# Seeed_Studio_Round_Display_for_XIAO_v1_0.net
KiCad netlist of a schematic drawn in EAGLE
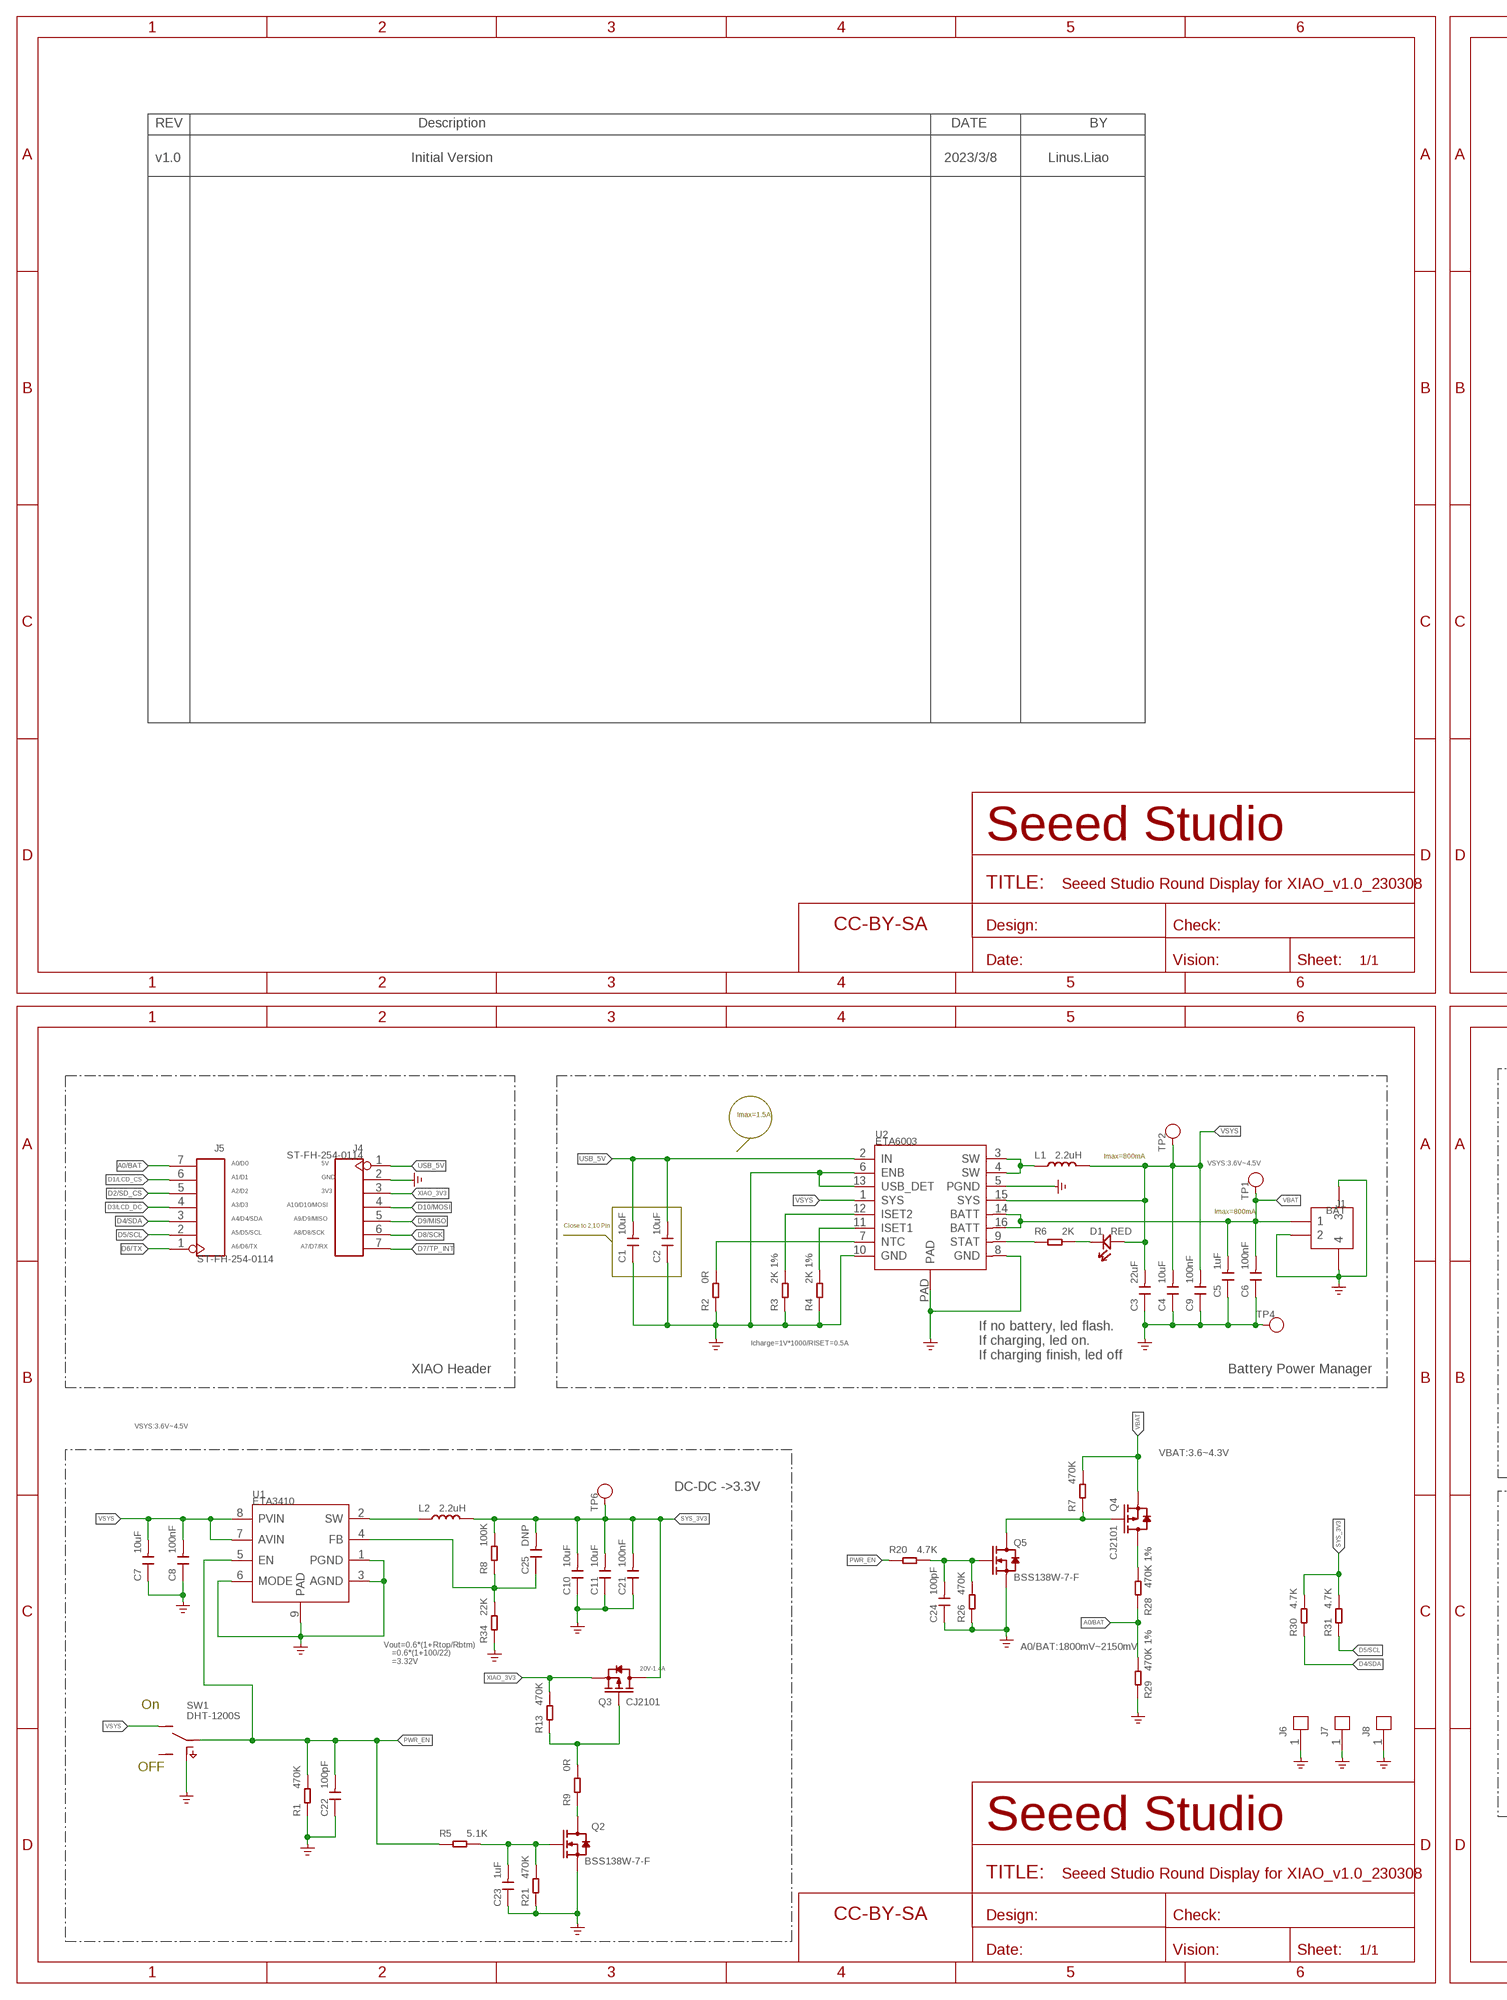
[diagram p0: schematic, sheet 1, part 1 of 2]
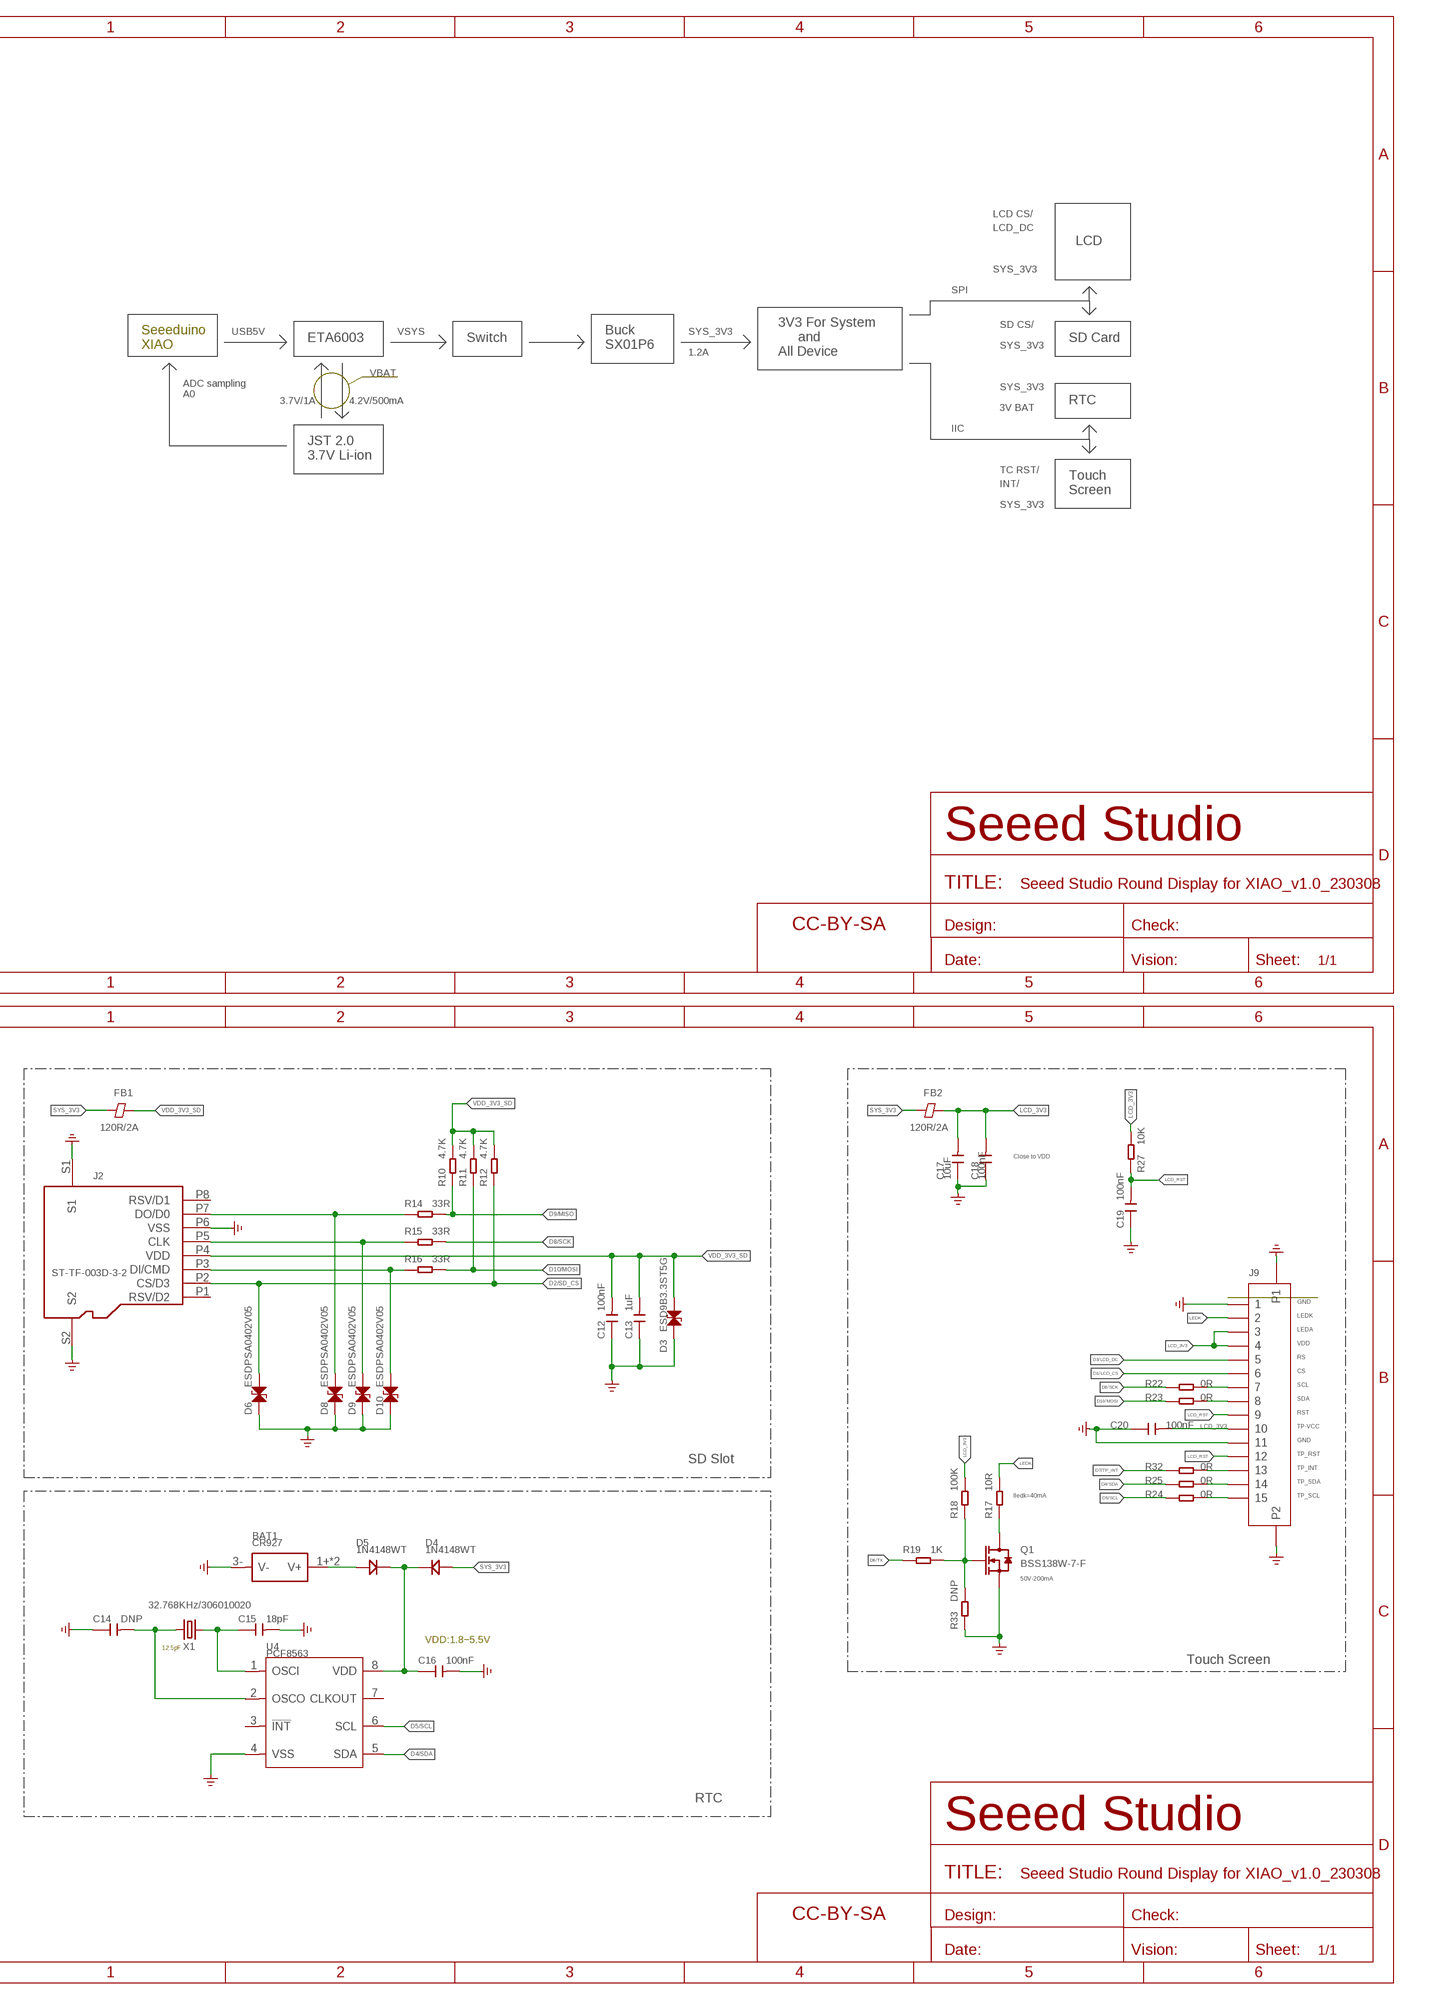
[diagram p1: schematic, sheet 1, part 2 of 2]

(export (version "E")
  (design (tool "Eeschema 10.0.6"))
  (components
    (comp (ref "BAT1")
      (value "CR927")
      (footprint "eagle-import:BAT2P-SMD-15.3X8.6X2.9MM")
      (libsource (lib "eagle-import") (part "BAT-HOLDER-CR927"))
    )
    (comp (ref "C1")
      (value "10uF")
      (footprint "eagle-import:C0603")
      (libsource (lib "eagle-import") (part "CAP-0603"))
    )
    (comp (ref "C2")
      (value "10uF")
      (footprint "eagle-import:C0603")
      (libsource (lib "eagle-import") (part "CAP-0603"))
    )
    (comp (ref "C3")
      (value "22uF")
      (footprint "eagle-import:C0603")
      (libsource (lib "eagle-import") (part "CAP-0603"))
    )
    (comp (ref "C4")
      (value "10uF")
      (footprint "eagle-import:C0603")
      (libsource (lib "eagle-import") (part "CAP-0603"))
    )
    (comp (ref "C5")
      (value "1uF")
      (footprint "eagle-import:C0402")
      (libsource (lib "eagle-import") (part "CAP-0402"))
    )
    (comp (ref "C6")
      (value "100nF")
      (footprint "eagle-import:C0402")
      (libsource (lib "eagle-import") (part "CAP-0402"))
    )
    (comp (ref "C7")
      (value "10uF")
      (footprint "eagle-import:C0603")
      (libsource (lib "eagle-import") (part "CAP-0603"))
    )
    (comp (ref "C8")
      (value "100nF")
      (footprint "eagle-import:C0402")
      (libsource (lib "eagle-import") (part "CAP-0402"))
    )
    (comp (ref "C9")
      (value "100nF")
      (footprint "eagle-import:C0402")
      (libsource (lib "eagle-import") (part "CAP-0402"))
    )
    (comp (ref "C10")
      (value "10uF")
      (footprint "eagle-import:C0603")
      (libsource (lib "eagle-import") (part "CAP-0603"))
    )
    (comp (ref "C11")
      (value "10uF")
      (footprint "eagle-import:C0603")
      (libsource (lib "eagle-import") (part "CAP-0603"))
    )
    (comp (ref "C12")
      (value "100nF")
      (footprint "eagle-import:C0402")
      (libsource (lib "eagle-import") (part "CAP-0402"))
    )
    (comp (ref "C13")
      (value "1uF")
      (footprint "eagle-import:C0402")
      (libsource (lib "eagle-import") (part "CAP-0402"))
    )
    (comp (ref "C14")
      (value "DNP")
      (footprint "eagle-import:C0402")
      (libsource (lib "eagle-import") (part "CAP-0402"))
    )
    (comp (ref "C15")
      (value "18pF")
      (footprint "eagle-import:C0402")
      (libsource (lib "eagle-import") (part "CAP-0402"))
    )
    (comp (ref "C16")
      (value "100nF")
      (footprint "eagle-import:C0402")
      (libsource (lib "eagle-import") (part "CAP-0402"))
    )
    (comp (ref "C17")
      (value "10uF")
      (footprint "eagle-import:C0402")
      (libsource (lib "eagle-import") (part "CAP-0402"))
    )
    (comp (ref "C18")
      (value "100nF")
      (footprint "eagle-import:C0402")
      (libsource (lib "eagle-import") (part "CAP-0402"))
    )
    (comp (ref "C19")
      (value "100nF")
      (footprint "eagle-import:C0402")
      (libsource (lib "eagle-import") (part "CAP-0402"))
    )
    (comp (ref "C20")
      (value "100nF")
      (footprint "eagle-import:C0402")
      (libsource (lib "eagle-import") (part "CAP-0402"))
    )
    (comp (ref "C21")
      (value "100nF")
      (footprint "eagle-import:C0402")
      (libsource (lib "eagle-import") (part "CAP-0402"))
    )
    (comp (ref "C22")
      (value "100pF")
      (footprint "eagle-import:C0402")
      (libsource (lib "eagle-import") (part "CAP-0402"))
    )
    (comp (ref "C23")
      (value "1uF")
      (footprint "eagle-import:C0402")
      (libsource (lib "eagle-import") (part "CAP-0402"))
    )
    (comp (ref "C24")
      (value "100pF")
      (footprint "eagle-import:C0402")
      (libsource (lib "eagle-import") (part "CAP-0402"))
    )
    (comp (ref "C25")
      (value "DNP")
      (footprint "eagle-import:C0402")
      (libsource (lib "eagle-import") (part "CAP-0402"))
    )
    (comp (ref "D1")
      (value "RED")
      (footprint "eagle-import:LED-0402")
      (libsource (lib "eagle-import") (part "LED-0402"))
    )
    (comp (ref "D3")
      (value "ESD9B3.3ST5G")
      (footprint "eagle-import:ESD-0402")
      (libsource (lib "eagle-import") (part "D-ESD-2P-DOUBLE-0402"))
    )
    (comp (ref "D4")
      (value "1N4148WT")
      (footprint "eagle-import:SOD-523")
      (libsource (lib "eagle-import") (part "DIODE'0603'"))
    )
    (comp (ref "D5")
      (value "1N4148WT")
      (footprint "eagle-import:SOD-523")
      (libsource (lib "eagle-import") (part "DIODE'0603'"))
    )
    (comp (ref "D6")
      (value "ESDPSA0402V05")
      (footprint "eagle-import:ESD-0402")
      (libsource (lib "eagle-import") (part "D-ESD-2P-DOUBLE-0402"))
    )
    (comp (ref "D8")
      (value "ESDPSA0402V05")
      (footprint "eagle-import:ESD-0402")
      (libsource (lib "eagle-import") (part "D-ESD-2P-DOUBLE-0402"))
    )
    (comp (ref "D9")
      (value "ESDPSA0402V05")
      (footprint "eagle-import:ESD-0402")
      (libsource (lib "eagle-import") (part "D-ESD-2P-DOUBLE-0402"))
    )
    (comp (ref "D10")
      (value "ESDPSA0402V05")
      (footprint "eagle-import:ESD-0402")
      (libsource (lib "eagle-import") (part "D-ESD-2P-DOUBLE-0402"))
    )
    (comp (ref "FB1")
      (value "120R/2A")
      (footprint "eagle-import:F0402")
      (libsource (lib "eagle-import") (part "FERRITE-BEAD-0402"))
    )
    (comp (ref "FB2")
      (value "120R/2A")
      (footprint "eagle-import:F0402")
      (libsource (lib "eagle-import") (part "FERRITE-BEAD-0402"))
    )
    (comp (ref "FR1")
      (value "SEEEDSTUDIO-OPEN-SCH-FRAME")
      (footprint "eagle-import:SEEEDSTUDIO-PCB-FRAME")
      (libsource (lib "eagle-import") (part "SEEEDSTUDIO-OPEN-SCH-FRAME"))
    )
    (comp (ref "FR2")
      (value "SEEEDSTUDIO-OPEN-SCH-FRAME")
      (footprint "eagle-import:SEEEDSTUDIO-PCB-FRAME")
      (libsource (lib "eagle-import") (part "SEEEDSTUDIO-OPEN-SCH-FRAME"))
    )
    (comp (ref "FR3")
      (value "SEEEDSTUDIO-OPEN-SCH-FRAME")
      (footprint "eagle-import:SEEEDSTUDIO-PCB-FRAME")
      (libsource (lib "eagle-import") (part "SEEEDSTUDIO-OPEN-SCH-FRAME"))
    )
    (comp (ref "FR4")
      (value "SEEEDSTUDIO-OPEN-SCH-FRAME")
      (footprint "eagle-import:SEEEDSTUDIO-PCB-FRAME")
      (libsource (lib "eagle-import") (part "SEEEDSTUDIO-OPEN-SCH-FRAME"))
    )
    (comp (ref "J1")
      (value "BAT")
      (footprint "eagle-import:HW2+2P-SMD-1.25")
      (libsource (lib "eagle-import") (part "JST-2+2P-1.25"))
    )
    (comp (ref "J2")
      (value "ST-TF-003D-3-2")
      (footprint "eagle-import:MICRO-SD8+2P-SMD-1.1-11.41X4.9X3MM")
      (libsource (lib "eagle-import") (part "MICRO-SD-CARD-HOLDER-SHORT-8P"))
    )
    (comp (ref "J4")
      (value "ST-FH-254-0114")
      (footprint "eagle-import:H7-2.54-18.28X2.5X5MM")
      (libsource (lib "eagle-import") (part "HEADER-7P-18.28X2.5"))
    )
    (comp (ref "J5")
      (value "ST-FH-254-0114")
      (footprint "eagle-import:H7-2.54-18.28X2.5X5MM")
      (libsource (lib "eagle-import") (part "HEADER-7P-18.28X2.5"))
    )
    (comp (ref "J6")
      (value "HEADER-1P-3.5/2.2_PASTE")
      (footprint "eagle-import:H1P-3.5_2.2MM-PASTE")
      (libsource (lib "eagle-import") (part "HEADER-1P-3.5/2.2_PASTE"))
    )
    (comp (ref "J7")
      (value "HEADER-1P-3.5/2.2_PASTE")
      (footprint "eagle-import:H1P-3.5_2.2MM-PASTE")
      (libsource (lib "eagle-import") (part "HEADER-1P-3.5/2.2_PASTE"))
    )
    (comp (ref "J8")
      (value "HEADER-1P-3.5/2.2_PASTE")
      (footprint "eagle-import:H1P-3.5_2.2MM-PASTE")
      (libsource (lib "eagle-import") (part "HEADER-1P-3.5/2.2_PASTE"))
    )
    (comp (ref "J9")
      (value "FPC-CONNECTOR-15P")
      (footprint "eagle-import:FPC15P-0.6-6.1X2.83X1MM")
      (libsource (lib "eagle-import") (part "FPC-CONNECTOR-15P"))
    )
    (comp (ref "L1")
      (value "2.2uH")
      (footprint "eagle-import:L0806")
      (libsource (lib "eagle-import") (part "INDUCTOR'0806'"))
    )
    (comp (ref "L2")
      (value "2.2uH")
      (footprint "eagle-import:L0806")
      (libsource (lib "eagle-import") (part "INDUCTOR'0806'"))
    )
    (comp (ref "Q1")
      (value "BSS138W-7-F")
      (footprint "eagle-import:SOT-323")
      (libsource (lib "eagle-import") (part "MOSFET-N-SI1304BDL"))
    )
    (comp (ref "Q2")
      (value "BSS138W-7-F")
      (footprint "eagle-import:SOT-323")
      (libsource (lib "eagle-import") (part "MOSFET-N-SI1304BDL"))
    )
    (comp (ref "Q3")
      (value "CJ2101")
      (footprint "eagle-import:SOT-323")
      (libsource (lib "eagle-import") (part "MOSFET-P-SOT323"))
    )
    (comp (ref "Q4")
      (value "CJ2101")
      (footprint "eagle-import:SOT-323")
      (libsource (lib "eagle-import") (part "MOSFET-P-SOT323"))
    )
    (comp (ref "Q5")
      (value "BSS138W-7-F")
      (footprint "eagle-import:SOT-323")
      (libsource (lib "eagle-import") (part "MOSFET-N-SI1304BDL"))
    )
    (comp (ref "R1")
      (value "470K")
      (footprint "eagle-import:R0402")
      (libsource (lib "eagle-import") (part "RES-0402"))
    )
    (comp (ref "R2")
      (value "0R")
      (footprint "eagle-import:R0402")
      (libsource (lib "eagle-import") (part "RES-0402"))
    )
    (comp (ref "R3")
      (value "2K 1%")
      (footprint "eagle-import:R0402")
      (libsource (lib "eagle-import") (part "RES-0402"))
    )
    (comp (ref "R4")
      (value "2K 1%")
      (footprint "eagle-import:R0402")
      (libsource (lib "eagle-import") (part "RES-0402"))
    )
    (comp (ref "R5")
      (value "5.1K")
      (footprint "eagle-import:R0402")
      (libsource (lib "eagle-import") (part "RES-0402"))
    )
    (comp (ref "R6")
      (value "2K")
      (footprint "eagle-import:R0402")
      (libsource (lib "eagle-import") (part "RES-0402"))
    )
    (comp (ref "R7")
      (value "470K")
      (footprint "eagle-import:R0402")
      (libsource (lib "eagle-import") (part "RES-0402"))
    )
    (comp (ref "R8")
      (value "100K")
      (footprint "eagle-import:R0402")
      (libsource (lib "eagle-import") (part "RES-0402"))
    )
    (comp (ref "R9")
      (value "0R")
      (footprint "eagle-import:R0402")
      (libsource (lib "eagle-import") (part "RES-0402"))
    )
    (comp (ref "R10")
      (value "4.7K")
      (footprint "eagle-import:R0402")
      (libsource (lib "eagle-import") (part "RES-0402"))
    )
    (comp (ref "R11")
      (value "4.7K")
      (footprint "eagle-import:R0402")
      (libsource (lib "eagle-import") (part "RES-0402"))
    )
    (comp (ref "R12")
      (value "4.7K")
      (footprint "eagle-import:R0402")
      (libsource (lib "eagle-import") (part "RES-0402"))
    )
    (comp (ref "R13")
      (value "470K")
      (footprint "eagle-import:R0402")
      (libsource (lib "eagle-import") (part "RES-0402"))
    )
    (comp (ref "R14")
      (value "33R")
      (footprint "eagle-import:R0402")
      (libsource (lib "eagle-import") (part "RES-0402"))
    )
    (comp (ref "R15")
      (value "33R")
      (footprint "eagle-import:R0402")
      (libsource (lib "eagle-import") (part "RES-0402"))
    )
    (comp (ref "R16")
      (value "33R")
      (footprint "eagle-import:R0402")
      (libsource (lib "eagle-import") (part "RES-0402"))
    )
    (comp (ref "R17")
      (value "10R")
      (footprint "eagle-import:R0603")
      (libsource (lib "eagle-import") (part "RES-0603"))
    )
    (comp (ref "R18")
      (value "100K")
      (footprint "eagle-import:R0402")
      (libsource (lib "eagle-import") (part "RES-0402"))
    )
    (comp (ref "R19")
      (value "1K")
      (footprint "eagle-import:R0402")
      (libsource (lib "eagle-import") (part "RES-0402"))
    )
    (comp (ref "R20")
      (value "4.7K")
      (footprint "eagle-import:R0402")
      (libsource (lib "eagle-import") (part "RES-0402"))
    )
    (comp (ref "R21")
      (value "470K")
      (footprint "eagle-import:R0402")
      (libsource (lib "eagle-import") (part "RES-0402"))
    )
    (comp (ref "R22")
      (value "0R")
      (footprint "eagle-import:R0402")
      (libsource (lib "eagle-import") (part "RES-0402"))
    )
    (comp (ref "R23")
      (value "0R")
      (footprint "eagle-import:R0402")
      (libsource (lib "eagle-import") (part "RES-0402"))
    )
    (comp (ref "R24")
      (value "0R")
      (footprint "eagle-import:R0402")
      (libsource (lib "eagle-import") (part "RES-0402"))
    )
    (comp (ref "R25")
      (value "0R")
      (footprint "eagle-import:R0402")
      (libsource (lib "eagle-import") (part "RES-0402"))
    )
    (comp (ref "R26")
      (value "470K")
      (footprint "eagle-import:R0402")
      (libsource (lib "eagle-import") (part "RES-0402"))
    )
    (comp (ref "R27")
      (value "10K")
      (footprint "eagle-import:R0402")
      (libsource (lib "eagle-import") (part "RES-0402"))
    )
    (comp (ref "R28")
      (value "470K 1%")
      (footprint "eagle-import:R0402")
      (libsource (lib "eagle-import") (part "RES-0402"))
    )
    (comp (ref "R29")
      (value "470K 1%")
      (footprint "eagle-import:R0402")
      (libsource (lib "eagle-import") (part "RES-0402"))
    )
    (comp (ref "R30")
      (value "4.7K")
      (footprint "eagle-import:R0402")
      (libsource (lib "eagle-import") (part "RES-0402"))
    )
    (comp (ref "R31")
      (value "4.7K")
      (footprint "eagle-import:R0402")
      (libsource (lib "eagle-import") (part "RES-0402"))
    )
    (comp (ref "R32")
      (value "0R")
      (footprint "eagle-import:R0402")
      (libsource (lib "eagle-import") (part "RES-0402"))
    )
    (comp (ref "R33")
      (value "DNP")
      (footprint "eagle-import:R0402")
      (libsource (lib "eagle-import") (part "RES-0402"))
    )
    (comp (ref "R34")
      (value "22K")
      (footprint "eagle-import:R0402")
      (libsource (lib "eagle-import") (part "RES-0402"))
    )
    (comp (ref "SW1")
      (value "DHT-1200S")
      (footprint "eagle-import:SW7-SMD-6.7X2.6X1.4MM-90D")
      (libsource (lib "eagle-import") (part "SWITCH-3+4P-311030002"))
    )
    (comp (ref "TP1")
      (value "TEST-POINT'4545'")
      (footprint "eagle-import:TP-D45MIL")
      (fields (field (name "PARTNO") "DNP"))
      (libsource (lib "eagle-import") (part "TEST-POINT'4545'"))
    )
    (comp (ref "TP2")
      (value "TEST-POINT'4545'")
      (footprint "eagle-import:TP-D45MIL")
      (fields (field (name "PARTNO") "DNP"))
      (libsource (lib "eagle-import") (part "TEST-POINT'4545'"))
    )
    (comp (ref "TP4")
      (value "TEST-POINT'4545'")
      (footprint "eagle-import:TP-D45MIL")
      (fields (field (name "PARTNO") "DNP"))
      (libsource (lib "eagle-import") (part "TEST-POINT'4545'"))
    )
    (comp (ref "TP6")
      (value "TEST-POINT'4545'")
      (footprint "eagle-import:TP-D45MIL")
      (fields (field (name "PARTNO") "DNP"))
      (libsource (lib "eagle-import") (part "TEST-POINT'4545'"))
    )
    (comp (ref "U1")
      (value "ETA3410")
      (footprint "eagle-import:DFN8G-0.5-2X2MM")
      (libsource (lib "eagle-import") (part "PMIC-ETA3410"))
    )
    (comp (ref "U2")
      (value "ETA6003")
      (footprint "eagle-import:QFN16GA-0.5-3X3MM")
      (libsource (lib "eagle-import") (part "PMIC-ETA6003-310990023"))
    )
    (comp (ref "U4")
      (value "PCF8563")
      (footprint "eagle-import:SOP8-1.27-5X3.9MM")
      (libsource (lib "eagle-import") (part "RTC-PCF8563T"))
    )
    (comp (ref "X1")
      (value "32.768KHz/306010020")
      (footprint "eagle-import:X2-SMD-L2.0X1.2X0.55MM")
      (libsource (lib "eagle-import") (part "CRYSTAL-2P'NX2012SA'"))
    )
  )
  (nets
    (net (code "1") (name "A0{slash}BAT") (class "Default")
      (node (ref "J5") (pin "7") (pinfunction "7_7") (pintype "bidirectional"))
      (node (ref "R28") (pin "1") (pinfunction "1_1") (pintype "passive"))
      (node (ref "R29") (pin "2") (pinfunction "2_2") (pintype "passive"))
    )
    (net (code "2") (name "D1{slash}LCD_CS") (class "Default")
      (node (ref "J5") (pin "6") (pinfunction "6_6") (pintype "bidirectional"))
      (node (ref "J9") (pin "6") (pinfunction "6_6") (pintype "bidirectional"))
    )
    (net (code "3") (name "D2{slash}SD_CS") (class "Default")
      (node (ref "D6") (pin "2") (pinfunction "2_2") (pintype "bidirectional"))
      (node (ref "J2") (pin "P2") (pinfunction "CS/D3_P2") (pintype "bidirectional"))
      (node (ref "J5") (pin "5") (pinfunction "5_5") (pintype "bidirectional"))
      (node (ref "R12") (pin "1") (pinfunction "1_1") (pintype "passive"))
    )
    (net (code "4") (name "D3{slash}LCD_DC") (class "Default")
      (node (ref "J5") (pin "4") (pinfunction "4_4") (pintype "bidirectional"))
      (node (ref "J9") (pin "5") (pinfunction "5_5") (pintype "bidirectional"))
    )
    (net (code "5") (name "D4{slash}SDA") (class "Default")
      (node (ref "J5") (pin "3") (pinfunction "3_3") (pintype "bidirectional"))
      (node (ref "R25") (pin "1") (pinfunction "1_1") (pintype "passive"))
      (node (ref "R30") (pin "1") (pinfunction "1_1") (pintype "passive"))
      (node (ref "U4") (pin "5") (pinfunction "SDA_5") (pintype "bidirectional"))
    )
    (net (code "6") (name "D5{slash}SCL") (class "Default")
      (node (ref "J5") (pin "2") (pinfunction "2_2") (pintype "bidirectional"))
      (node (ref "R24") (pin "1") (pinfunction "1_1") (pintype "passive"))
      (node (ref "R31") (pin "1") (pinfunction "1_1") (pintype "passive"))
      (node (ref "U4") (pin "6") (pinfunction "SCL_6") (pintype "bidirectional"))
    )
    (net (code "7") (name "D6{slash}TX") (class "Default")
      (node (ref "J5") (pin "1") (pinfunction "1_1") (pintype "bidirectional"))
      (node (ref "R19") (pin "1") (pinfunction "1_1") (pintype "passive"))
    )
    (net (code "8") (name "D7{slash}TP_INT") (class "Default")
      (node (ref "J4") (pin "7") (pinfunction "7_7") (pintype "bidirectional"))
      (node (ref "R32") (pin "1") (pinfunction "1_1") (pintype "passive"))
    )
    (net (code "9") (name "D8{slash}SCK") (class "Default")
      (node (ref "J4") (pin "6") (pinfunction "6_6") (pintype "bidirectional"))
      (node (ref "R15") (pin "2") (pinfunction "2_2") (pintype "passive"))
      (node (ref "R22") (pin "1") (pinfunction "1_1") (pintype "passive"))
    )
    (net (code "10") (name "D9{slash}MISO") (class "Default")
      (node (ref "J4") (pin "5") (pinfunction "5_5") (pintype "bidirectional"))
      (node (ref "R10") (pin "1") (pinfunction "1_1") (pintype "passive"))
      (node (ref "R14") (pin "2") (pinfunction "2_2") (pintype "passive"))
    )
    (net (code "11") (name "D10{slash}MOSI") (class "Default")
      (node (ref "J4") (pin "4") (pinfunction "4_4") (pintype "bidirectional"))
      (node (ref "R11") (pin "1") (pinfunction "1_1") (pintype "passive"))
      (node (ref "R16") (pin "2") (pinfunction "2_2") (pintype "passive"))
      (node (ref "R23") (pin "1") (pinfunction "1_1") (pintype "passive"))
    )
    (net (code "12") (name "GND_POWER") (class "Default")
      (node (ref "BAT1") (pin "3-") (pinfunction "V-_3-") (pintype "bidirectional"))
      (node (ref "C1") (pin "1") (pinfunction "1_1") (pintype "passive"))
      (node (ref "C10") (pin "1") (pinfunction "1_1") (pintype "passive"))
      (node (ref "C11") (pin "1") (pinfunction "1_1") (pintype "passive"))
      (node (ref "C12") (pin "1") (pinfunction "1_1") (pintype "passive"))
      (node (ref "C13") (pin "1") (pinfunction "1_1") (pintype "passive"))
      (node (ref "C14") (pin "1") (pinfunction "1_1") (pintype "passive"))
      (node (ref "C15") (pin "2") (pinfunction "2_2") (pintype "passive"))
      (node (ref "C16") (pin "2") (pinfunction "2_2") (pintype "passive"))
      (node (ref "C17") (pin "1") (pinfunction "1_1") (pintype "passive"))
      (node (ref "C18") (pin "1") (pinfunction "1_1") (pintype "passive"))
      (node (ref "C19") (pin "1") (pinfunction "1_1") (pintype "passive"))
      (node (ref "C2") (pin "1") (pinfunction "1_1") (pintype "passive"))
      (node (ref "C20") (pin "1") (pinfunction "1_1") (pintype "passive"))
      (node (ref "C21") (pin "1") (pinfunction "1_1") (pintype "passive"))
      (node (ref "C22") (pin "1") (pinfunction "1_1") (pintype "passive"))
      (node (ref "C23") (pin "1") (pinfunction "1_1") (pintype "passive"))
      (node (ref "C24") (pin "1") (pinfunction "1_1") (pintype "passive"))
      (node (ref "C3") (pin "1") (pinfunction "1_1") (pintype "passive"))
      (node (ref "C4") (pin "1") (pinfunction "1_1") (pintype "passive"))
      (node (ref "C5") (pin "1") (pinfunction "1_1") (pintype "passive"))
      (node (ref "C6") (pin "1") (pinfunction "1_1") (pintype "passive"))
      (node (ref "C7") (pin "1") (pinfunction "1_1") (pintype "passive"))
      (node (ref "C8") (pin "1") (pinfunction "1_1") (pintype "passive"))
      (node (ref "C9") (pin "1") (pinfunction "1_1") (pintype "passive"))
      (node (ref "D10") (pin "1") (pinfunction "1_1") (pintype "bidirectional"))
      (node (ref "D3") (pin "1") (pinfunction "1_1") (pintype "bidirectional"))
      (node (ref "D6") (pin "1") (pinfunction "1_1") (pintype "bidirectional"))
      (node (ref "D8") (pin "1") (pinfunction "1_1") (pintype "bidirectional"))
      (node (ref "D9") (pin "1") (pinfunction "1_1") (pintype "bidirectional"))
      (node (ref "J1") (pin "2") (pinfunction "2_2") (pintype "bidirectional"))
      (node (ref "J1") (pin "P1") (pinfunction "3_P1") (pintype "bidirectional"))
      (node (ref "J1") (pin "P2") (pinfunction "4_P2") (pintype "bidirectional"))
      (node (ref "J2") (pin "P6") (pinfunction "VSS_P6") (pintype "bidirectional"))
      (node (ref "J2") (pin "S1") (pinfunction "S1_S1") (pintype "bidirectional"))
      (node (ref "J2") (pin "S2") (pinfunction "S2_S2") (pintype "bidirectional"))
      (node (ref "J4") (pin "2") (pinfunction "2_2") (pintype "bidirectional"))
      (node (ref "J6") (pin "1") (pinfunction "1_1") (pintype "bidirectional"))
      (node (ref "J7") (pin "1") (pinfunction "1_1") (pintype "bidirectional"))
      (node (ref "J8") (pin "1") (pinfunction "1_1") (pintype "bidirectional"))
      (node (ref "J9") (pin "1") (pinfunction "1_1") (pintype "bidirectional"))
      (node (ref "J9") (pin "11") (pinfunction "11_11") (pintype "bidirectional"))
      (node (ref "J9") (pin "16") (pinfunction "P1_16") (pintype "bidirectional"))
      (node (ref "J9") (pin "17") (pinfunction "P2_17") (pintype "bidirectional"))
      (node (ref "Q1") (pin "2") (pinfunction "S_2") (pintype "passive"))
      (node (ref "Q2") (pin "2") (pinfunction "S_2") (pintype "passive"))
      (node (ref "Q5") (pin "2") (pinfunction "S_2") (pintype "passive"))
      (node (ref "R1") (pin "1") (pinfunction "1_1") (pintype "passive"))
      (node (ref "R2") (pin "1") (pinfunction "1_1") (pintype "passive"))
      (node (ref "R21") (pin "1") (pinfunction "1_1") (pintype "passive"))
      (node (ref "R26") (pin "1") (pinfunction "1_1") (pintype "passive"))
      (node (ref "R29") (pin "1") (pinfunction "1_1") (pintype "passive"))
      (node (ref "R3") (pin "1") (pinfunction "1_1") (pintype "passive"))
      (node (ref "R33") (pin "1") (pinfunction "1_1") (pintype "passive"))
      (node (ref "R34") (pin "1") (pinfunction "1_1") (pintype "passive"))
      (node (ref "R4") (pin "1") (pinfunction "1_1") (pintype "passive"))
      (node (ref "SW1") (pin "P1") (pinfunction "SS2_P1") (pintype "bidirectional"))
      (node (ref "SW1") (pin "P2") (pinfunction "SS2_P2") (pintype "bidirectional"))
      (node (ref "SW1") (pin "P3") (pinfunction "SS2_P3") (pintype "bidirectional"))
      (node (ref "SW1") (pin "P4") (pinfunction "SS2_P4") (pintype "bidirectional"))
      (node (ref "TP4") (pin "T") (pinfunction "T_T") (pintype "bidirectional"))
      (node (ref "U1") (pin "1") (pinfunction "PGND_1") (pintype "bidirectional"))
      (node (ref "U1") (pin "3") (pinfunction "AGND_3") (pintype "bidirectional"))
      (node (ref "U1") (pin "6") (pinfunction "MODE_6") (pintype "bidirectional"))
      (node (ref "U1") (pin "9") (pinfunction "PAD_9") (pintype "bidirectional"))
      (node (ref "U2") (pin "10") (pinfunction "GND_10") (pintype "bidirectional"))
      (node (ref "U2") (pin "13") (pinfunction "USB_DET_13") (pintype "bidirectional"))
      (node (ref "U2") (pin "5") (pinfunction "PGND_5") (pintype "bidirectional"))
      (node (ref "U2") (pin "6") (pinfunction "ENB_6") (pintype "bidirectional"))
      (node (ref "U2") (pin "8") (pinfunction "GND_8") (pintype "bidirectional"))
      (node (ref "U2") (pin "PAD") (pinfunction "PAD_PAD") (pintype "bidirectional"))
      (node (ref "U4") (pin "4") (pinfunction "VSS_4") (pintype "bidirectional"))
    )
    (net (code "13") (name "LCD_3V3") (class "Default")
      (node (ref "C17") (pin "2") (pinfunction "2_2") (pintype "passive"))
      (node (ref "C18") (pin "2") (pinfunction "2_2") (pintype "passive"))
      (node (ref "C20") (pin "2") (pinfunction "2_2") (pintype "passive"))
      (node (ref "FB2") (pin "2") (pinfunction "2_2") (pintype "bidirectional"))
      (node (ref "J9") (pin "10") (pinfunction "10_10") (pintype "bidirectional"))
      (node (ref "J9") (pin "3") (pinfunction "3_3") (pintype "bidirectional"))
      (node (ref "J9") (pin "4") (pinfunction "4_4") (pintype "bidirectional"))
      (node (ref "R18") (pin "2") (pinfunction "2_2") (pintype "passive"))
      (node (ref "R27") (pin "2") (pinfunction "2_2") (pintype "passive"))
    )
    (net (code "14") (name "LCD_RST") (class "Default")
      (node (ref "C19") (pin "2") (pinfunction "2_2") (pintype "passive"))
      (node (ref "J9") (pin "12") (pinfunction "12_12") (pintype "bidirectional"))
      (node (ref "J9") (pin "9") (pinfunction "9_9") (pintype "bidirectional"))
      (node (ref "R27") (pin "1") (pinfunction "1_1") (pintype "passive"))
    )
    (net (code "15") (name "LEDK") (class "Default")
      (node (ref "J9") (pin "2") (pinfunction "2_2") (pintype "bidirectional"))
      (node (ref "R17") (pin "2") (pinfunction "2_2") (pintype "passive"))
    )
    (net (code "16") (name "Net-(BAT1-V+-Pad1+)") (class "Default")
      (node (ref "BAT1") (pin "1+") (pinfunction "V+_1+") (pintype "bidirectional"))
      (node (ref "BAT1") (pin "2+") (pinfunction "V+_2+") (pintype "bidirectional"))
      (node (ref "D5") (pin "+") (pinfunction "+_+") (pintype "passive"))
    )
    (net (code "17") (name "Net-(D1-Pad-)") (class "Default")
      (node (ref "D1") (pin "-") (pinfunction "-_-") (pintype "passive"))
      (node (ref "R6") (pin "2") (pinfunction "2_2") (pintype "passive"))
    )
    (net (code "18") (name "Net-(J2-CLK)") (class "Default")
      (node (ref "D9") (pin "2") (pinfunction "2_2") (pintype "bidirectional"))
      (node (ref "J2") (pin "P5") (pinfunction "CLK_P5") (pintype "bidirectional"))
      (node (ref "R15") (pin "1") (pinfunction "1_1") (pintype "passive"))
    )
    (net (code "19") (name "Net-(J2-DI{slash}CMD)") (class "Default")
      (node (ref "D10") (pin "2") (pinfunction "2_2") (pintype "bidirectional"))
      (node (ref "J2") (pin "P3") (pinfunction "DI/CMD_P3") (pintype "bidirectional"))
      (node (ref "R16") (pin "1") (pinfunction "1_1") (pintype "passive"))
    )
    (net (code "20") (name "Net-(J2-DO{slash}D0)") (class "Default")
      (node (ref "D8") (pin "2") (pinfunction "2_2") (pintype "bidirectional"))
      (node (ref "J2") (pin "P7") (pinfunction "DO/D0_P7") (pintype "bidirectional"))
      (node (ref "R14") (pin "1") (pinfunction "1_1") (pintype "passive"))
    )
    (net (code "21") (name "Net-(J9-Pad7)") (class "Default")
      (node (ref "J9") (pin "7") (pinfunction "7_7") (pintype "bidirectional"))
      (node (ref "R22") (pin "2") (pinfunction "2_2") (pintype "passive"))
    )
    (net (code "22") (name "Net-(J9-Pad8)") (class "Default")
      (node (ref "J9") (pin "8") (pinfunction "8_8") (pintype "bidirectional"))
      (node (ref "R23") (pin "2") (pinfunction "2_2") (pintype "passive"))
    )
    (net (code "23") (name "Net-(J9-Pad13)") (class "Default")
      (node (ref "J9") (pin "13") (pinfunction "13_13") (pintype "bidirectional"))
      (node (ref "R32") (pin "2") (pinfunction "2_2") (pintype "passive"))
    )
    (net (code "24") (name "Net-(J9-Pad14)") (class "Default")
      (node (ref "J9") (pin "14") (pinfunction "14_14") (pintype "bidirectional"))
      (node (ref "R25") (pin "2") (pinfunction "2_2") (pintype "passive"))
    )
    (net (code "25") (name "Net-(J9-Pad15)") (class "Default")
      (node (ref "J9") (pin "15") (pinfunction "15_15") (pintype "bidirectional"))
      (node (ref "R24") (pin "2") (pinfunction "2_2") (pintype "passive"))
    )
    (net (code "26") (name "Net-(L1-Pad1)") (class "Default")
      (node (ref "L1") (pin "1") (pinfunction "1_1") (pintype "passive"))
      (node (ref "U2") (pin "3") (pinfunction "SW_3") (pintype "bidirectional"))
      (node (ref "U2") (pin "4") (pinfunction "SW_4") (pintype "bidirectional"))
    )
    (net (code "27") (name "Net-(Q1-D)") (class "Default")
      (node (ref "Q1") (pin "3") (pinfunction "D_3") (pintype "passive"))
      (node (ref "R17") (pin "1") (pinfunction "1_1") (pintype "passive"))
    )
    (net (code "28") (name "Net-(Q1-G)") (class "Default")
      (node (ref "Q1") (pin "1") (pinfunction "G_1") (pintype "passive"))
      (node (ref "R18") (pin "1") (pinfunction "1_1") (pintype "passive"))
      (node (ref "R19") (pin "2") (pinfunction "2_2") (pintype "passive"))
      (node (ref "R33") (pin "2") (pinfunction "2_2") (pintype "passive"))
    )
    (net (code "29") (name "Net-(Q2-D)") (class "Default")
      (node (ref "Q2") (pin "3") (pinfunction "D_3") (pintype "passive"))
      (node (ref "R9") (pin "1") (pinfunction "1_1") (pintype "passive"))
    )
    (net (code "30") (name "Net-(Q2-G)") (class "Default")
      (node (ref "C23") (pin "2") (pinfunction "2_2") (pintype "passive"))
      (node (ref "Q2") (pin "1") (pinfunction "G_1") (pintype "passive"))
      (node (ref "R21") (pin "2") (pinfunction "2_2") (pintype "passive"))
      (node (ref "R5") (pin "2") (pinfunction "2_2") (pintype "passive"))
    )
    (net (code "31") (name "Net-(Q3-G)") (class "Default")
      (node (ref "Q3") (pin "1") (pinfunction "G_1") (pintype "passive"))
      (node (ref "R13") (pin "1") (pinfunction "1_1") (pintype "passive"))
      (node (ref "R9") (pin "2") (pinfunction "2_2") (pintype "passive"))
    )
    (net (code "32") (name "Net-(Q4-D)") (class "Default")
      (node (ref "Q4") (pin "3") (pinfunction "D_3") (pintype "passive"))
      (node (ref "R28") (pin "2") (pinfunction "2_2") (pintype "passive"))
    )
    (net (code "33") (name "Net-(Q4-G)") (class "Default")
      (node (ref "Q4") (pin "1") (pinfunction "G_1") (pintype "passive"))
      (node (ref "Q5") (pin "3") (pinfunction "D_3") (pintype "passive"))
      (node (ref "R7") (pin "1") (pinfunction "1_1") (pintype "passive"))
    )
    (net (code "34") (name "Net-(Q5-G)") (class "Default")
      (node (ref "C24") (pin "2") (pinfunction "2_2") (pintype "passive"))
      (node (ref "Q5") (pin "1") (pinfunction "G_1") (pintype "passive"))
      (node (ref "R20") (pin "2") (pinfunction "2_2") (pintype "passive"))
      (node (ref "R26") (pin "2") (pinfunction "2_2") (pintype "passive"))
    )
    (net (code "35") (name "Net-(U1-FB)") (class "Default")
      (node (ref "C25") (pin "1") (pinfunction "1_1") (pintype "passive"))
      (node (ref "R34") (pin "2") (pinfunction "2_2") (pintype "passive"))
      (node (ref "R8") (pin "1") (pinfunction "1_1") (pintype "passive"))
      (node (ref "U1") (pin "4") (pinfunction "FB_4") (pintype "bidirectional"))
    )
    (net (code "36") (name "Net-(U1-SW)") (class "Default")
      (node (ref "L2") (pin "1") (pinfunction "1_1") (pintype "passive"))
      (node (ref "U1") (pin "2") (pinfunction "SW_2") (pintype "bidirectional"))
    )
    (net (code "37") (name "Net-(U2-ISET1)") (class "Default")
      (node (ref "R4") (pin "2") (pinfunction "2_2") (pintype "passive"))
      (node (ref "U2") (pin "11") (pinfunction "ISET1_11") (pintype "bidirectional"))
    )
    (net (code "38") (name "Net-(U2-ISET2)") (class "Default")
      (node (ref "R3") (pin "2") (pinfunction "2_2") (pintype "passive"))
      (node (ref "U2") (pin "12") (pinfunction "ISET2_12") (pintype "bidirectional"))
    )
    (net (code "39") (name "Net-(U2-NTC)") (class "Default")
      (node (ref "R2") (pin "2") (pinfunction "2_2") (pintype "passive"))
      (node (ref "U2") (pin "7") (pinfunction "NTC_7") (pintype "bidirectional"))
    )
    (net (code "40") (name "Net-(U2-STAT)") (class "Default")
      (node (ref "R6") (pin "1") (pinfunction "1_1") (pintype "passive"))
      (node (ref "U2") (pin "9") (pinfunction "STAT_9") (pintype "bidirectional"))
    )
    (net (code "41") (name "Net-(U4-OSCI)") (class "Default")
      (node (ref "C15") (pin "1") (pinfunction "1_1") (pintype "passive"))
      (node (ref "U4") (pin "1") (pinfunction "OSCI_1") (pintype "bidirectional"))
      (node (ref "X1") (pin "2") (pinfunction "2_2") (pintype "passive"))
    )
    (net (code "42") (name "Net-(U4-OSCO)") (class "Default")
      (node (ref "C14") (pin "2") (pinfunction "2_2") (pintype "passive"))
      (node (ref "U4") (pin "2") (pinfunction "OSCO_2") (pintype "bidirectional"))
      (node (ref "X1") (pin "1") (pinfunction "1_1") (pintype "passive"))
    )
    (net (code "43") (name "Net-(U4-VDD)") (class "Default")
      (node (ref "C16") (pin "1") (pinfunction "1_1") (pintype "passive"))
      (node (ref "D4") (pin "-") (pinfunction "-_-") (pintype "passive"))
      (node (ref "D5") (pin "-") (pinfunction "-_-") (pintype "passive"))
      (node (ref "U4") (pin "8") (pinfunction "VDD_8") (pintype "bidirectional"))
    )
    (net (code "44") (name "PWR_EN") (class "Default")
      (node (ref "C22") (pin "2") (pinfunction "2_2") (pintype "passive"))
      (node (ref "R1") (pin "2") (pinfunction "2_2") (pintype "passive"))
      (node (ref "R20") (pin "1") (pinfunction "1_1") (pintype "passive"))
      (node (ref "R5") (pin "1") (pinfunction "1_1") (pintype "passive"))
      (node (ref "SW1") (pin "2") (pinfunction "COM_2") (pintype "bidirectional"))
      (node (ref "U1") (pin "5") (pinfunction "EN_5") (pintype "bidirectional"))
    )
    (net (code "45") (name "SYS_3V3") (class "Default")
      (node (ref "C10") (pin "2") (pinfunction "2_2") (pintype "passive"))
      (node (ref "C11") (pin "2") (pinfunction "2_2") (pintype "passive"))
      (node (ref "C21") (pin "2") (pinfunction "2_2") (pintype "passive"))
      (node (ref "C25") (pin "2") (pinfunction "2_2") (pintype "passive"))
      (node (ref "D4") (pin "+") (pinfunction "+_+") (pintype "passive"))
      (node (ref "FB1") (pin "1") (pinfunction "1_1") (pintype "bidirectional"))
      (node (ref "FB2") (pin "1") (pinfunction "1_1") (pintype "bidirectional"))
      (node (ref "L2") (pin "2") (pinfunction "2_2") (pintype "passive"))
      (node (ref "Q3") (pin "3") (pinfunction "D_3") (pintype "passive"))
      (node (ref "R30") (pin "2") (pinfunction "2_2") (pintype "passive"))
      (node (ref "R31") (pin "2") (pinfunction "2_2") (pintype "passive"))
      (node (ref "R8") (pin "2") (pinfunction "2_2") (pintype "passive"))
      (node (ref "TP6") (pin "T") (pinfunction "T_T") (pintype "bidirectional"))
    )
    (net (code "46") (name "USB_5V") (class "Default")
      (node (ref "C1") (pin "2") (pinfunction "2_2") (pintype "passive"))
      (node (ref "C2") (pin "2") (pinfunction "2_2") (pintype "passive"))
      (node (ref "J4") (pin "1") (pinfunction "1_1") (pintype "bidirectional"))
      (node (ref "U2") (pin "2") (pinfunction "IN_2") (pintype "bidirectional"))
    )
    (net (code "47") (name "VBAT") (class "Default")
      (node (ref "C5") (pin "2") (pinfunction "2_2") (pintype "passive"))
      (node (ref "C6") (pin "2") (pinfunction "2_2") (pintype "passive"))
      (node (ref "J1") (pin "1") (pinfunction "1_1") (pintype "bidirectional"))
      (node (ref "Q4") (pin "2") (pinfunction "S_2") (pintype "passive"))
      (node (ref "R7") (pin "2") (pinfunction "2_2") (pintype "passive"))
      (node (ref "TP1") (pin "T") (pinfunction "T_T") (pintype "bidirectional"))
      (node (ref "U2") (pin "14") (pinfunction "BATT_14") (pintype "bidirectional"))
      (node (ref "U2") (pin "16") (pinfunction "BATT_16") (pintype "bidirectional"))
    )
    (net (code "48") (name "VDD_3V3_SD") (class "Default")
      (node (ref "C12") (pin "2") (pinfunction "2_2") (pintype "passive"))
      (node (ref "C13") (pin "2") (pinfunction "2_2") (pintype "passive"))
      (node (ref "D3") (pin "2") (pinfunction "2_2") (pintype "bidirectional"))
      (node (ref "FB1") (pin "2") (pinfunction "2_2") (pintype "bidirectional"))
      (node (ref "J2") (pin "P4") (pinfunction "VDD_P4") (pintype "bidirectional"))
      (node (ref "R10") (pin "2") (pinfunction "2_2") (pintype "passive"))
      (node (ref "R11") (pin "2") (pinfunction "2_2") (pintype "passive"))
      (node (ref "R12") (pin "2") (pinfunction "2_2") (pintype "passive"))
    )
    (net (code "49") (name "VSYS") (class "Default")
      (node (ref "C3") (pin "2") (pinfunction "2_2") (pintype "passive"))
      (node (ref "C4") (pin "2") (pinfunction "2_2") (pintype "passive"))
      (node (ref "C7") (pin "2") (pinfunction "2_2") (pintype "passive"))
      (node (ref "C8") (pin "2") (pinfunction "2_2") (pintype "passive"))
      (node (ref "C9") (pin "2") (pinfunction "2_2") (pintype "passive"))
      (node (ref "D1") (pin "+") (pinfunction "+_+") (pintype "passive"))
      (node (ref "L1") (pin "2") (pinfunction "2_2") (pintype "passive"))
      (node (ref "SW1") (pin "1") (pinfunction "A_1") (pintype "bidirectional"))
      (node (ref "TP2") (pin "T") (pinfunction "T_T") (pintype "bidirectional"))
      (node (ref "U1") (pin "7") (pinfunction "AVIN_7") (pintype "bidirectional"))
      (node (ref "U1") (pin "8") (pinfunction "PVIN_8") (pintype "bidirectional"))
      (node (ref "U2") (pin "1") (pinfunction "SYS_1") (pintype "bidirectional"))
      (node (ref "U2") (pin "15") (pinfunction "SYS_15") (pintype "bidirectional"))
    )
    (net (code "50") (name "XIAO_3V3") (class "Default")
      (node (ref "J4") (pin "3") (pinfunction "3_3") (pintype "bidirectional"))
      (node (ref "Q3") (pin "2") (pinfunction "S_2") (pintype "passive"))
      (node (ref "R13") (pin "2") (pinfunction "2_2") (pintype "passive"))
    )
    (net (code "51") (name "unconnected-(J2-RSV{slash}D1-PadP8)") (class "Default")
      (node (ref "J2") (pin "P8") (pinfunction "RSV/D1_P8") (pintype "bidirectional"))
    )
    (net (code "52") (name "unconnected-(J2-RSV{slash}D2-PadP1)") (class "Default")
      (node (ref "J2") (pin "P1") (pinfunction "RSV/D2_P1") (pintype "bidirectional"))
    )
    (net (code "53") (name "unconnected-(SW1-B-Pad3)") (class "Default")
      (node (ref "SW1") (pin "3") (pinfunction "B_3") (pintype "bidirectional"))
    )
    (net (code "54") (name "unconnected-(U4-CLKOUT-Pad7)") (class "Default")
      (node (ref "U4") (pin "7") (pinfunction "CLKOUT_7") (pintype "bidirectional"))
    )
    (net (code "55") (name "unconnected-(U4-~{INT}-Pad3)") (class "Default")
      (node (ref "U4") (pin "3") (pinfunction "~{INT}_3") (pintype "bidirectional"))
    )
  )
)
